# power.net
KiCad netlist of a schematic drawn in EAGLE
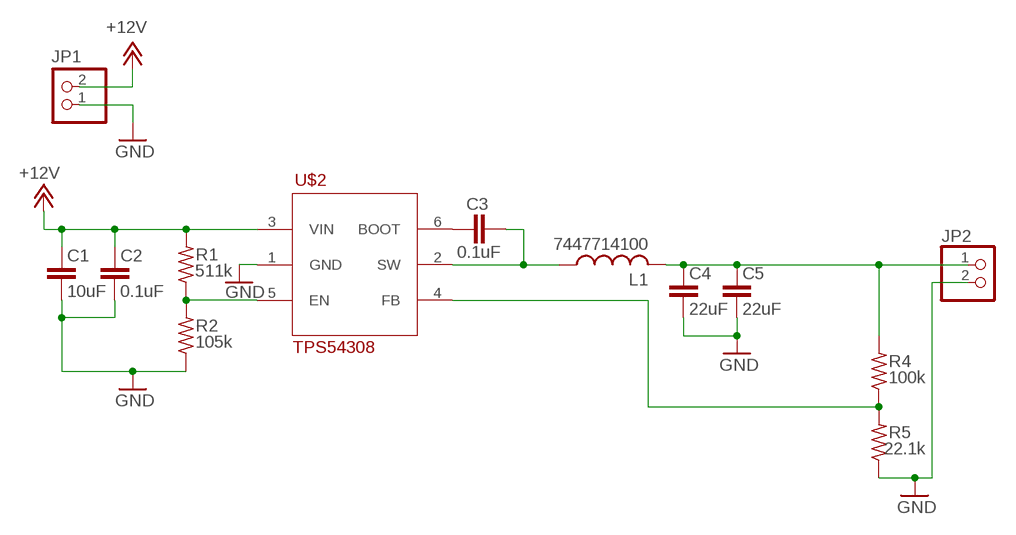
[diagram p0: schematic, sheet 1]

(export (version "E")
  (design (tool "Eeschema 10.0.6"))
  (components
    (comp (ref "C1")
      (value "10uF")
      (footprint "eagle-import:C2012")
      (libsource (lib "eagle-import") (part "C-EUC2012"))
    )
    (comp (ref "C2")
      (value "0.1uF")
      (footprint "eagle-import:C2012")
      (libsource (lib "eagle-import") (part "C-EUC2012"))
    )
    (comp (ref "C3")
      (value "0.1uF")
      (footprint "eagle-import:C2012")
      (libsource (lib "eagle-import") (part "C-EUC2012"))
    )
    (comp (ref "C4")
      (value "22uF")
      (footprint "eagle-import:C2012")
      (libsource (lib "eagle-import") (part "C-EUC2012"))
    )
    (comp (ref "C5")
      (value "22uF")
      (footprint "eagle-import:C2012")
      (libsource (lib "eagle-import") (part "C-EUC2012"))
    )
    (comp (ref "JP1")
      (value "PINHD-1X2")
      (footprint "eagle-import:1X02")
      (libsource (lib "eagle-import") (part "PINHD-1X2"))
    )
    (comp (ref "JP2")
      (value "PINHD-1X2")
      (footprint "eagle-import:1X02")
      (libsource (lib "eagle-import") (part "PINHD-1X2"))
    )
    (comp (ref "L1")
      (value "7447714100")
      (footprint "eagle-import:7447714100")
      (libsource (lib "eagle-import") (part "7447714100"))
    )
    (comp (ref "R1")
      (value "511k")
      (footprint "eagle-import:R0805")
      (libsource (lib "eagle-import") (part "R-US_R0805"))
    )
    (comp (ref "R2")
      (value "105k")
      (footprint "eagle-import:R0805")
      (libsource (lib "eagle-import") (part "R-US_R0805"))
    )
    (comp (ref "R4")
      (value "100k")
      (footprint "eagle-import:R0805")
      (libsource (lib "eagle-import") (part "R-US_R0805"))
    )
    (comp (ref "R5")
      (value "22.1k")
      (footprint "eagle-import:R0805")
      (libsource (lib "eagle-import") (part "R-US_R0805"))
    )
    (comp (ref "U$2")
      (value "TPS54308")
      (footprint "eagle-import:SOT-23-6")
      (libsource (lib "eagle-import") (part "TPS54308"))
    )
  )
  (nets
    (net (code "1") (name "+12V") (class "Default")
      (node (ref "C1") (pin "1") (pinfunction "1_1") (pintype "passive"))
      (node (ref "C2") (pin "1") (pinfunction "1_1") (pintype "passive"))
      (node (ref "JP1") (pin "2") (pinfunction "2_2") (pintype "passive"))
      (node (ref "R1") (pin "2") (pinfunction "2_2") (pintype "passive"))
      (node (ref "U$2") (pin "3") (pinfunction "VIN_3") (pintype "input"))
    )
    (net (code "2") (name "GND") (class "Default")
      (node (ref "C1") (pin "2") (pinfunction "2_2") (pintype "passive"))
      (node (ref "C2") (pin "2") (pinfunction "2_2") (pintype "passive"))
      (node (ref "C4") (pin "2") (pinfunction "2_2") (pintype "passive"))
      (node (ref "C5") (pin "2") (pinfunction "2_2") (pintype "passive"))
      (node (ref "JP1") (pin "1") (pinfunction "1_1") (pintype "passive"))
      (node (ref "JP2") (pin "2") (pinfunction "2_2") (pintype "passive"))
      (node (ref "R2") (pin "1") (pinfunction "1_1") (pintype "passive"))
      (node (ref "R5") (pin "1") (pinfunction "1_1") (pintype "passive"))
      (node (ref "U$2") (pin "1") (pinfunction "GND_1") (pintype "bidirectional"))
    )
    (net (code "3") (name "Net-(L1-1)") (class "Default")
      (node (ref "C3") (pin "2") (pinfunction "2_2") (pintype "passive"))
      (node (ref "L1") (pin "P$1") (pinfunction "1_P$1") (pintype "passive"))
      (node (ref "U$2") (pin "2") (pinfunction "SW_2") (pintype "bidirectional"))
    )
    (net (code "4") (name "Net-(L1-2)") (class "Default")
      (node (ref "C4") (pin "1") (pinfunction "1_1") (pintype "passive"))
      (node (ref "C5") (pin "1") (pinfunction "1_1") (pintype "passive"))
      (node (ref "JP2") (pin "1") (pinfunction "1_1") (pintype "passive"))
      (node (ref "L1") (pin "P$2") (pinfunction "2_P$2") (pintype "passive"))
      (node (ref "R4") (pin "2") (pinfunction "2_2") (pintype "passive"))
    )
    (net (code "5") (name "Net-(U$2-BOOT)") (class "Default")
      (node (ref "C3") (pin "1") (pinfunction "1_1") (pintype "passive"))
      (node (ref "U$2") (pin "6") (pinfunction "BOOT_6") (pintype "bidirectional"))
    )
    (net (code "6") (name "Net-(U$2-EN)") (class "Default")
      (node (ref "R1") (pin "1") (pinfunction "1_1") (pintype "passive"))
      (node (ref "R2") (pin "2") (pinfunction "2_2") (pintype "passive"))
      (node (ref "U$2") (pin "5") (pinfunction "EN_5") (pintype "input"))
    )
    (net (code "7") (name "Net-(U$2-FB)") (class "Default")
      (node (ref "R4") (pin "1") (pinfunction "1_1") (pintype "passive"))
      (node (ref "R5") (pin "2") (pinfunction "2_2") (pintype "passive"))
      (node (ref "U$2") (pin "4") (pinfunction "FB_4") (pintype "bidirectional"))
    )
  )
)
